# MotherBoard.net
KiCad netlist of a schematic drawn in EAGLE
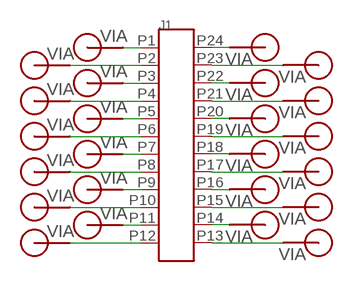
[diagram p0: schematic, sheet 1]

(export (version "E")
  (design (tool "Eeschema 10.0.6"))
  (components
    (comp (ref "J1")
      (value "EBM12DRXH")
      (footprint "eagle-import:EBM12DRXH")
      (libsource (lib "eagle-import") (part "EBM12DRXH"))
    )
    (comp (ref "V1")
      (value "VIA60MIL-SQ")
      (footprint "eagle-import:VIA-60MIL-SQ")
      (libsource (lib "eagle-import") (part "VIA60MIL-SQ"))
    )
    (comp (ref "V2")
      (value "VIA60MIL-SQ")
      (footprint "eagle-import:VIA-60MIL-SQ")
      (libsource (lib "eagle-import") (part "VIA60MIL-SQ"))
    )
    (comp (ref "V3")
      (value "VIA60MIL-SQ")
      (footprint "eagle-import:VIA-60MIL-SQ")
      (libsource (lib "eagle-import") (part "VIA60MIL-SQ"))
    )
    (comp (ref "V4")
      (value "VIA60MIL-SQ")
      (footprint "eagle-import:VIA-60MIL-SQ")
      (libsource (lib "eagle-import") (part "VIA60MIL-SQ"))
    )
    (comp (ref "V5")
      (value "VIA60MIL-SQ")
      (footprint "eagle-import:VIA-60MIL-SQ")
      (libsource (lib "eagle-import") (part "VIA60MIL-SQ"))
    )
    (comp (ref "V6")
      (value "VIA60MIL-SQ")
      (footprint "eagle-import:VIA-60MIL-SQ")
      (libsource (lib "eagle-import") (part "VIA60MIL-SQ"))
    )
    (comp (ref "V7")
      (value "VIA60MIL-SQ")
      (footprint "eagle-import:VIA-60MIL-SQ")
      (libsource (lib "eagle-import") (part "VIA60MIL-SQ"))
    )
    (comp (ref "V8")
      (value "VIA60MIL-SQ")
      (footprint "eagle-import:VIA-60MIL-SQ")
      (libsource (lib "eagle-import") (part "VIA60MIL-SQ"))
    )
    (comp (ref "V9")
      (value "VIA60MIL-SQ")
      (footprint "eagle-import:VIA-60MIL-SQ")
      (libsource (lib "eagle-import") (part "VIA60MIL-SQ"))
    )
    (comp (ref "V10")
      (value "VIA60MIL-SQ")
      (footprint "eagle-import:VIA-60MIL-SQ")
      (libsource (lib "eagle-import") (part "VIA60MIL-SQ"))
    )
    (comp (ref "V11")
      (value "VIA60MIL-SQ")
      (footprint "eagle-import:VIA-60MIL-SQ")
      (libsource (lib "eagle-import") (part "VIA60MIL-SQ"))
    )
    (comp (ref "V12")
      (value "VIA60MIL-SQ")
      (footprint "eagle-import:VIA-60MIL-SQ")
      (libsource (lib "eagle-import") (part "VIA60MIL-SQ"))
    )
    (comp (ref "V13")
      (value "VIA60MIL-SQ")
      (footprint "eagle-import:VIA-60MIL-SQ")
      (libsource (lib "eagle-import") (part "VIA60MIL-SQ"))
    )
    (comp (ref "V14")
      (value "VIA60MIL-SQ")
      (footprint "eagle-import:VIA-60MIL-SQ")
      (libsource (lib "eagle-import") (part "VIA60MIL-SQ"))
    )
    (comp (ref "V15")
      (value "VIA60MIL-SQ")
      (footprint "eagle-import:VIA-60MIL-SQ")
      (libsource (lib "eagle-import") (part "VIA60MIL-SQ"))
    )
    (comp (ref "V16")
      (value "VIA60MIL-SQ")
      (footprint "eagle-import:VIA-60MIL-SQ")
      (libsource (lib "eagle-import") (part "VIA60MIL-SQ"))
    )
    (comp (ref "V17")
      (value "VIA60MIL-SQ")
      (footprint "eagle-import:VIA-60MIL-SQ")
      (libsource (lib "eagle-import") (part "VIA60MIL-SQ"))
    )
    (comp (ref "V18")
      (value "VIA60MIL-SQ")
      (footprint "eagle-import:VIA-60MIL-SQ")
      (libsource (lib "eagle-import") (part "VIA60MIL-SQ"))
    )
    (comp (ref "V19")
      (value "VIA60MIL-SQ")
      (footprint "eagle-import:VIA-60MIL-SQ")
      (libsource (lib "eagle-import") (part "VIA60MIL-SQ"))
    )
    (comp (ref "V20")
      (value "VIA60MIL-SQ")
      (footprint "eagle-import:VIA-60MIL-SQ")
      (libsource (lib "eagle-import") (part "VIA60MIL-SQ"))
    )
    (comp (ref "V21")
      (value "VIA60MIL-SQ")
      (footprint "eagle-import:VIA-60MIL-SQ")
      (libsource (lib "eagle-import") (part "VIA60MIL-SQ"))
    )
    (comp (ref "V22")
      (value "VIA60MIL-SQ")
      (footprint "eagle-import:VIA-60MIL-SQ")
      (libsource (lib "eagle-import") (part "VIA60MIL-SQ"))
    )
    (comp (ref "V23")
      (value "VIA60MIL-SQ")
      (footprint "eagle-import:VIA-60MIL-SQ")
      (libsource (lib "eagle-import") (part "VIA60MIL-SQ"))
    )
    (comp (ref "V24")
      (value "VIA60MIL-SQ")
      (footprint "eagle-import:VIA-60MIL-SQ")
      (libsource (lib "eagle-import") (part "VIA60MIL-SQ"))
    )
  )
  (nets
    (net (code "1") (name "Net-(J1-P$1)") (class "Default")
      (node (ref "J1") (pin "P1") (pinfunction "P$1_P1") (pintype "bidirectional"))
      (node (ref "V1") (pin "P$1") (pinfunction "P$1_P$1") (pintype "bidirectional"))
    )
    (net (code "2") (name "Net-(J1-P$2)") (class "Default")
      (node (ref "J1") (pin "P2") (pinfunction "P$2_P2") (pintype "bidirectional"))
      (node (ref "V2") (pin "P$1") (pinfunction "P$1_P$1") (pintype "bidirectional"))
    )
    (net (code "3") (name "Net-(J1-P$3)") (class "Default")
      (node (ref "J1") (pin "P3") (pinfunction "P$3_P3") (pintype "bidirectional"))
      (node (ref "V3") (pin "P$1") (pinfunction "P$1_P$1") (pintype "bidirectional"))
    )
    (net (code "4") (name "Net-(J1-P$4)") (class "Default")
      (node (ref "J1") (pin "P4") (pinfunction "P$4_P4") (pintype "bidirectional"))
      (node (ref "V4") (pin "P$1") (pinfunction "P$1_P$1") (pintype "bidirectional"))
    )
    (net (code "5") (name "Net-(J1-P$5)") (class "Default")
      (node (ref "J1") (pin "P5") (pinfunction "P$5_P5") (pintype "bidirectional"))
      (node (ref "V5") (pin "P$1") (pinfunction "P$1_P$1") (pintype "bidirectional"))
    )
    (net (code "6") (name "Net-(J1-P$6)") (class "Default")
      (node (ref "J1") (pin "P6") (pinfunction "P$6_P6") (pintype "bidirectional"))
      (node (ref "V6") (pin "P$1") (pinfunction "P$1_P$1") (pintype "bidirectional"))
    )
    (net (code "7") (name "Net-(J1-P$7)") (class "Default")
      (node (ref "J1") (pin "P7") (pinfunction "P$7_P7") (pintype "bidirectional"))
      (node (ref "V7") (pin "P$1") (pinfunction "P$1_P$1") (pintype "bidirectional"))
    )
    (net (code "8") (name "Net-(J1-P$8)") (class "Default")
      (node (ref "J1") (pin "P8") (pinfunction "P$8_P8") (pintype "bidirectional"))
      (node (ref "V8") (pin "P$1") (pinfunction "P$1_P$1") (pintype "bidirectional"))
    )
    (net (code "9") (name "Net-(J1-P$9)") (class "Default")
      (node (ref "J1") (pin "P9") (pinfunction "P$9_P9") (pintype "bidirectional"))
      (node (ref "V9") (pin "P$1") (pinfunction "P$1_P$1") (pintype "bidirectional"))
    )
    (net (code "10") (name "Net-(J1-P$10)") (class "Default")
      (node (ref "J1") (pin "P10") (pinfunction "P$10_P10") (pintype "bidirectional"))
      (node (ref "V10") (pin "P$1") (pinfunction "P$1_P$1") (pintype "bidirectional"))
    )
    (net (code "11") (name "Net-(J1-P$11)") (class "Default")
      (node (ref "J1") (pin "P11") (pinfunction "P$11_P11") (pintype "bidirectional"))
      (node (ref "V11") (pin "P$1") (pinfunction "P$1_P$1") (pintype "bidirectional"))
    )
    (net (code "12") (name "Net-(J1-P$12)") (class "Default")
      (node (ref "J1") (pin "P12") (pinfunction "P$12_P12") (pintype "bidirectional"))
      (node (ref "V12") (pin "P$1") (pinfunction "P$1_P$1") (pintype "bidirectional"))
    )
    (net (code "13") (name "Net-(J1-P$13)") (class "Default")
      (node (ref "J1") (pin "P13") (pinfunction "P$13_P13") (pintype "bidirectional"))
      (node (ref "V13") (pin "P$1") (pinfunction "P$1_P$1") (pintype "bidirectional"))
    )
    (net (code "14") (name "Net-(J1-P$14)") (class "Default")
      (node (ref "J1") (pin "P14") (pinfunction "P$14_P14") (pintype "bidirectional"))
      (node (ref "V14") (pin "P$1") (pinfunction "P$1_P$1") (pintype "bidirectional"))
    )
    (net (code "15") (name "Net-(J1-P$15)") (class "Default")
      (node (ref "J1") (pin "P15") (pinfunction "P$15_P15") (pintype "bidirectional"))
      (node (ref "V15") (pin "P$1") (pinfunction "P$1_P$1") (pintype "bidirectional"))
    )
    (net (code "16") (name "Net-(J1-P$16)") (class "Default")
      (node (ref "J1") (pin "P16") (pinfunction "P$16_P16") (pintype "bidirectional"))
      (node (ref "V16") (pin "P$1") (pinfunction "P$1_P$1") (pintype "bidirectional"))
    )
    (net (code "17") (name "Net-(J1-P$17)") (class "Default")
      (node (ref "J1") (pin "P17") (pinfunction "P$17_P17") (pintype "bidirectional"))
      (node (ref "V17") (pin "P$1") (pinfunction "P$1_P$1") (pintype "bidirectional"))
    )
    (net (code "18") (name "Net-(J1-P$18)") (class "Default")
      (node (ref "J1") (pin "P18") (pinfunction "P$18_P18") (pintype "bidirectional"))
      (node (ref "V18") (pin "P$1") (pinfunction "P$1_P$1") (pintype "bidirectional"))
    )
    (net (code "19") (name "Net-(J1-P$19)") (class "Default")
      (node (ref "J1") (pin "P19") (pinfunction "P$19_P19") (pintype "bidirectional"))
      (node (ref "V19") (pin "P$1") (pinfunction "P$1_P$1") (pintype "bidirectional"))
    )
    (net (code "20") (name "Net-(J1-P$20)") (class "Default")
      (node (ref "J1") (pin "P20") (pinfunction "P$20_P20") (pintype "bidirectional"))
      (node (ref "V20") (pin "P$1") (pinfunction "P$1_P$1") (pintype "bidirectional"))
    )
    (net (code "21") (name "Net-(J1-P$21)") (class "Default")
      (node (ref "J1") (pin "P21") (pinfunction "P$21_P21") (pintype "bidirectional"))
      (node (ref "V21") (pin "P$1") (pinfunction "P$1_P$1") (pintype "bidirectional"))
    )
    (net (code "22") (name "Net-(J1-P$22)") (class "Default")
      (node (ref "J1") (pin "P22") (pinfunction "P$22_P22") (pintype "bidirectional"))
      (node (ref "V22") (pin "P$1") (pinfunction "P$1_P$1") (pintype "bidirectional"))
    )
    (net (code "23") (name "Net-(J1-P$23)") (class "Default")
      (node (ref "J1") (pin "P23") (pinfunction "P$23_P23") (pintype "bidirectional"))
      (node (ref "V23") (pin "P$1") (pinfunction "P$1_P$1") (pintype "bidirectional"))
    )
    (net (code "24") (name "Net-(J1-P$24)") (class "Default")
      (node (ref "J1") (pin "P24") (pinfunction "P$24_P24") (pintype "bidirectional"))
      (node (ref "V24") (pin "P$1") (pinfunction "P$1_P$1") (pintype "bidirectional"))
    )
  )
)
